# TBX01.net
KiCad netlist of a schematic drawn in EAGLE
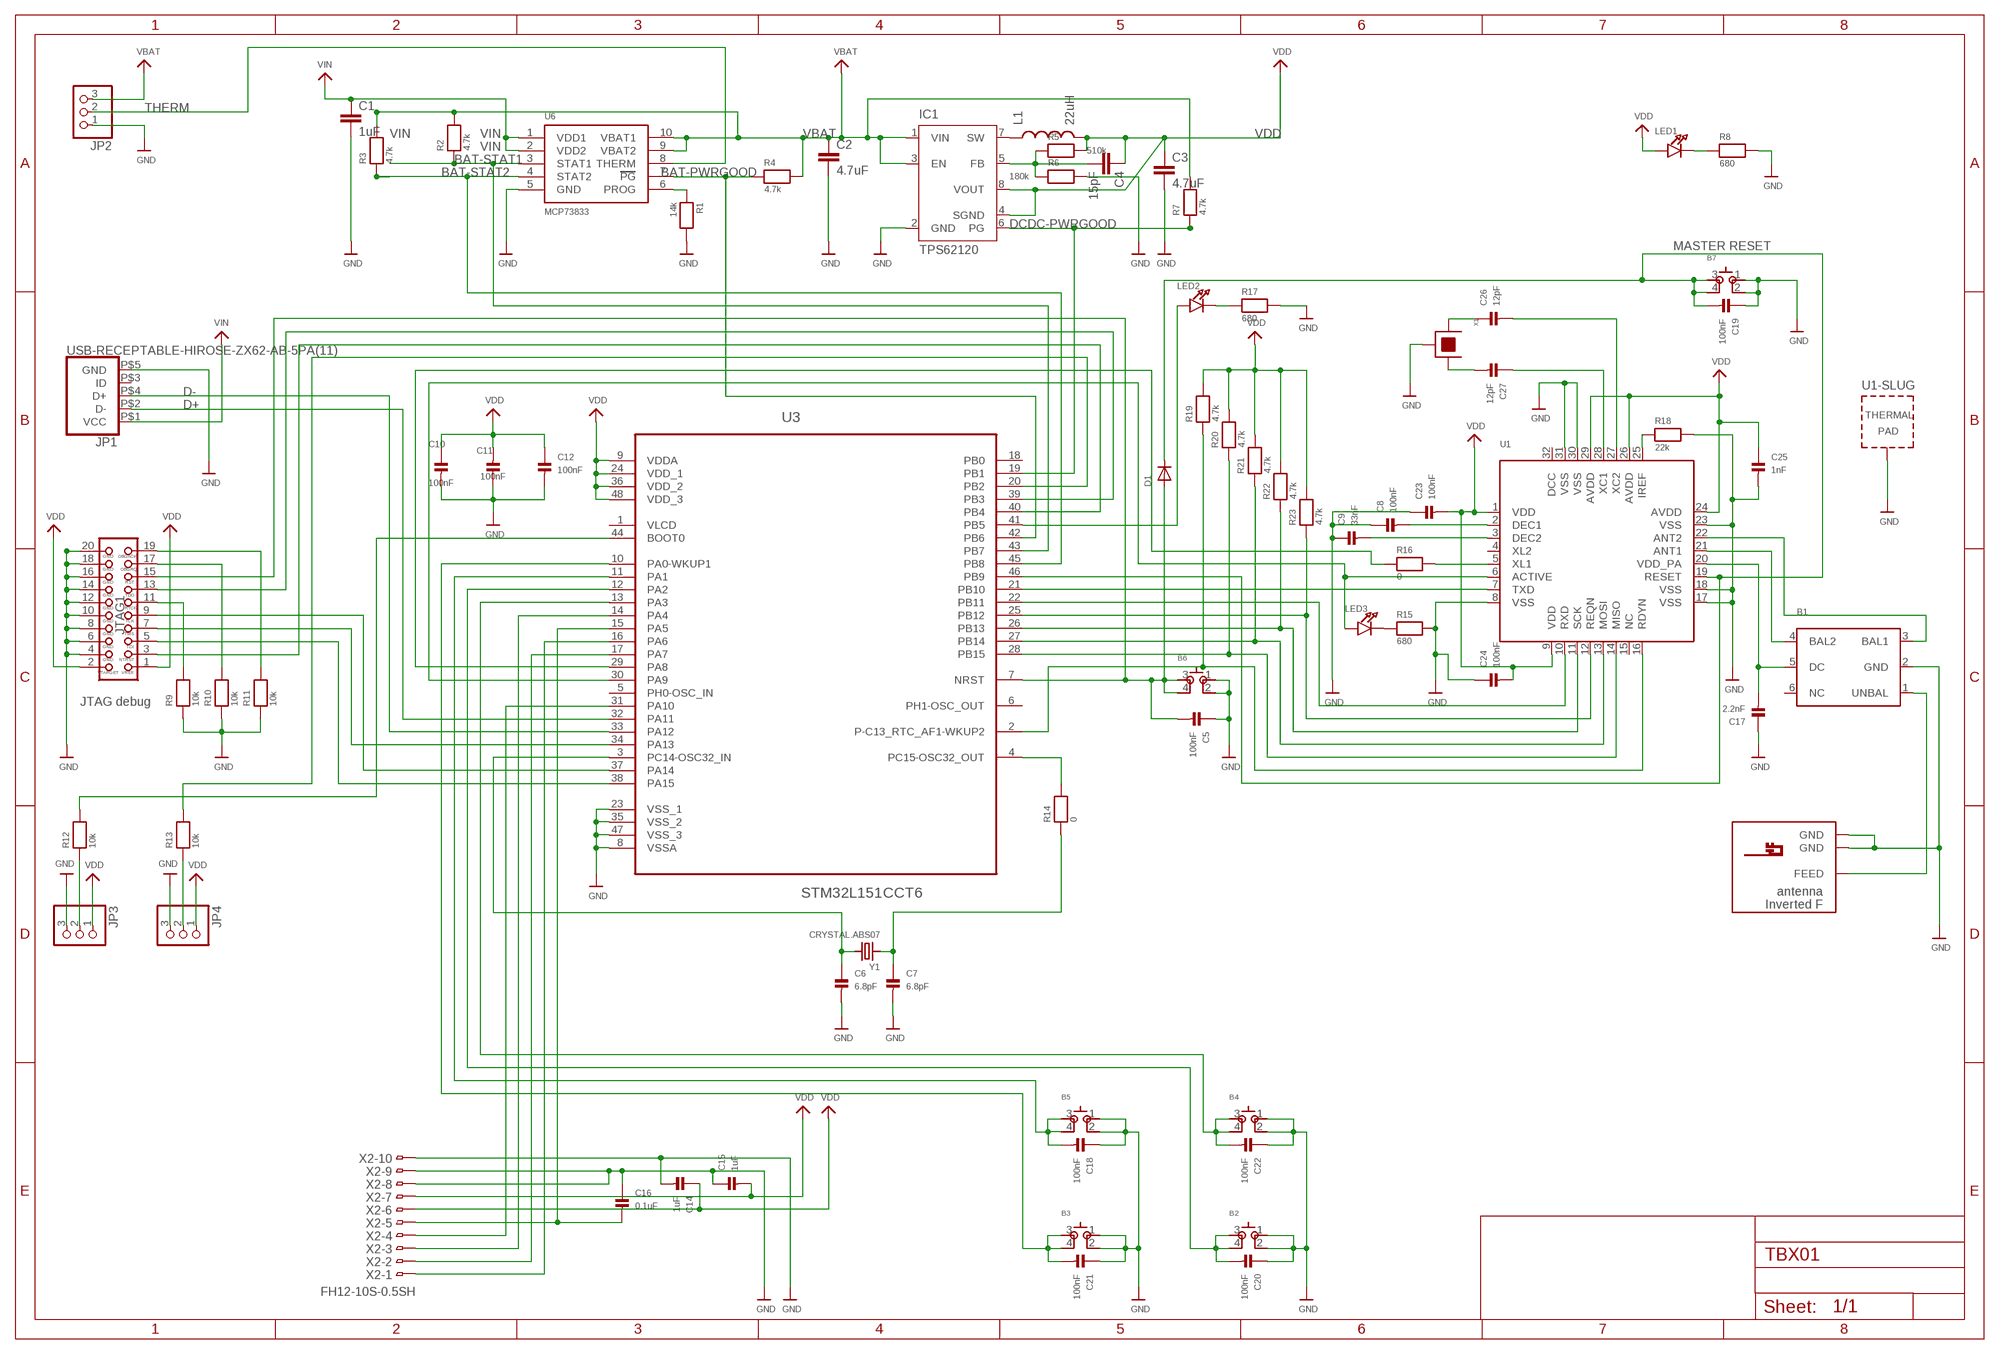
[diagram p0: schematic, sheet 1]

(export (version "E")
  (design (tool "Eeschema 10.0.6"))
  (components
    (comp (ref "B1")
      (value "BALUN+LP_NORDIC")
      (footprint "eagle-import:BALUN0603")
      (libsource (lib "eagle-import") (part "BALUN+LP_NORDIC"))
    )
    (comp (ref "B2")
      (value "SKSCLDE010")
      (footprint "eagle-import:SKSCLDE010")
      (libsource (lib "eagle-import") (part "SKSCLDE010"))
    )
    (comp (ref "B3")
      (value "SKSCLDE010")
      (footprint "eagle-import:SKSCLDE010")
      (libsource (lib "eagle-import") (part "SKSCLDE010"))
    )
    (comp (ref "B4")
      (value "SKSCLDE010")
      (footprint "eagle-import:SKSCLDE010")
      (libsource (lib "eagle-import") (part "SKSCLDE010"))
    )
    (comp (ref "B5")
      (value "SKSCLDE010")
      (footprint "eagle-import:SKSCLDE010")
      (libsource (lib "eagle-import") (part "SKSCLDE010"))
    )
    (comp (ref "B6")
      (value "SKSCLDE010")
      (footprint "eagle-import:SKSCLDE010")
      (libsource (lib "eagle-import") (part "SKSCLDE010"))
    )
    (comp (ref "B7")
      (value "SKSCLDE010")
      (footprint "eagle-import:SKSCLDE010")
      (libsource (lib "eagle-import") (part "SKSCLDE010"))
    )
    (comp (ref "C1")
      (value "1uF")
      (footprint "eagle-import:C0603")
      (libsource (lib "eagle-import") (part "C-EUC0603"))
    )
    (comp (ref "C2")
      (value "4.7uF")
      (footprint "eagle-import:C0603")
      (libsource (lib "eagle-import") (part "C-EUC0603"))
    )
    (comp (ref "C3")
      (value "4.7uF")
      (footprint "eagle-import:C0603")
      (libsource (lib "eagle-import") (part "C-EUC0603"))
    )
    (comp (ref "C4")
      (value "15pF")
      (footprint "eagle-import:C0603")
      (libsource (lib "eagle-import") (part "C-EUC0603"))
    )
    (comp (ref "C5")
      (value "100nF")
      (footprint "eagle-import:0603")
      (libsource (lib "eagle-import") (part "CAP_CERAMIC0603"))
    )
    (comp (ref "C6")
      (value "6.8pF")
      (footprint "eagle-import:0603")
      (libsource (lib "eagle-import") (part "CAP_CERAMIC0603"))
    )
    (comp (ref "C7")
      (value "6.8pF")
      (footprint "eagle-import:0603")
      (libsource (lib "eagle-import") (part "CAP_CERAMIC0603"))
    )
    (comp (ref "C8")
      (value "100nF")
      (footprint "eagle-import:0603")
      (libsource (lib "eagle-import") (part "CAP_CERAMIC0603"))
    )
    (comp (ref "C9")
      (value "33nF")
      (footprint "eagle-import:0603")
      (libsource (lib "eagle-import") (part "CAP_CERAMIC0603"))
    )
    (comp (ref "C10")
      (value "100nF")
      (footprint "eagle-import:0603")
      (libsource (lib "eagle-import") (part "CAP_CERAMIC0603"))
    )
    (comp (ref "C11")
      (value "100nF")
      (footprint "eagle-import:0603")
      (libsource (lib "eagle-import") (part "CAP_CERAMIC0603"))
    )
    (comp (ref "C12")
      (value "100nF")
      (footprint "eagle-import:0603")
      (libsource (lib "eagle-import") (part "CAP_CERAMIC0603"))
    )
    (comp (ref "C14")
      (value "1uF")
      (footprint "eagle-import:0603")
      (libsource (lib "eagle-import") (part "CAP_CERAMIC0603"))
    )
    (comp (ref "C15")
      (value "1uF")
      (footprint "eagle-import:0603")
      (libsource (lib "eagle-import") (part "CAP_CERAMIC0603"))
    )
    (comp (ref "C16")
      (value "0.1uF")
      (footprint "eagle-import:0603")
      (libsource (lib "eagle-import") (part "CAP_CERAMIC0603"))
    )
    (comp (ref "C17")
      (value "2.2nF")
      (footprint "eagle-import:0603")
      (libsource (lib "eagle-import") (part "CAP_CERAMIC0603"))
    )
    (comp (ref "C18")
      (value "100nF")
      (footprint "eagle-import:0603")
      (libsource (lib "eagle-import") (part "CAP_CERAMIC0603"))
    )
    (comp (ref "C19")
      (value "100nF")
      (footprint "eagle-import:0603")
      (libsource (lib "eagle-import") (part "CAP_CERAMIC0603"))
    )
    (comp (ref "C20")
      (value "100nF")
      (footprint "eagle-import:0603")
      (libsource (lib "eagle-import") (part "CAP_CERAMIC0603"))
    )
    (comp (ref "C21")
      (value "100nF")
      (footprint "eagle-import:0603")
      (libsource (lib "eagle-import") (part "CAP_CERAMIC0603"))
    )
    (comp (ref "C22")
      (value "100nF")
      (footprint "eagle-import:0603")
      (libsource (lib "eagle-import") (part "CAP_CERAMIC0603"))
    )
    (comp (ref "C23")
      (value "100nF")
      (footprint "eagle-import:0603")
      (libsource (lib "eagle-import") (part "CAP_CERAMIC0603"))
    )
    (comp (ref "C24")
      (value "100nF")
      (footprint "eagle-import:0603")
      (libsource (lib "eagle-import") (part "CAP_CERAMIC0603"))
    )
    (comp (ref "C25")
      (value "1nF")
      (footprint "eagle-import:0603")
      (libsource (lib "eagle-import") (part "CAP_CERAMIC0603"))
    )
    (comp (ref "C26")
      (value "12pF")
      (footprint "eagle-import:0603")
      (libsource (lib "eagle-import") (part "CAP_CERAMIC0603"))
    )
    (comp (ref "C27")
      (value "12pF")
      (footprint "eagle-import:0603")
      (libsource (lib "eagle-import") (part "CAP_CERAMIC0603"))
    )
    (comp (ref "D1")
      (value "DIODESOD-123")
      (footprint "eagle-import:SOD-123")
      (libsource (lib "eagle-import") (part "DIODESOD-123"))
    )
    (comp (ref "IC1")
      (value "TPS62120")
      (footprint "eagle-import:DCN-R-PDSO-G8")
      (libsource (lib "eagle-import") (part "TPS62120"))
    )
    (comp (ref "JP1")
      (value "USB-RECEPTABLE-HIROSE-ZX62-AB-5PA(11)")
      (footprint "eagle-import:HIROSE-ZX62-AB-5PA(11)")
      (libsource (lib "eagle-import") (part "USB-RECEPTABLE-HIROSE-ZX62-AB-5PA(11)"))
    )
    (comp (ref "JP2")
      (value "HEADER-1X3ROUND")
      (footprint "eagle-import:1X03_ROUND")
      (libsource (lib "eagle-import") (part "HEADER-1X3ROUND"))
    )
    (comp (ref "JP3")
      (value "HEADER-1X3ROUND")
      (footprint "eagle-import:1X03_ROUND")
      (libsource (lib "eagle-import") (part "HEADER-1X3ROUND"))
    )
    (comp (ref "JP4")
      (value "HEADER-1X3ROUND")
      (footprint "eagle-import:1X03_ROUND")
      (libsource (lib "eagle-import") (part "HEADER-1X3ROUND"))
    )
    (comp (ref "JTAG1")
      (value "JTAG-ARM")
      (footprint "eagle-import:JTAG-ARM")
      (libsource (lib "eagle-import") (part "JTAG-ARM"))
    )
    (comp (ref "L1")
      (value "22uH")
      (footprint "eagle-import:1210")
      (libsource (lib "eagle-import") (part "INDUCTOR1210"))
    )
    (comp (ref "LED1")
      (value "LED0603")
      (footprint "eagle-import:CHIPLED_0603")
      (libsource (lib "eagle-import") (part "LED0603"))
    )
    (comp (ref "LED2")
      (value "LED0603")
      (footprint "eagle-import:CHIPLED_0603")
      (libsource (lib "eagle-import") (part "LED0603"))
    )
    (comp (ref "LED3")
      (value "LED0603")
      (footprint "eagle-import:CHIPLED_0603")
      (libsource (lib "eagle-import") (part "LED0603"))
    )
    (comp (ref "R1")
      (value "14k")
      (footprint "eagle-import:0603")
      (libsource (lib "eagle-import") (part "RESISTOR0603"))
    )
    (comp (ref "R2")
      (value "4.7k")
      (footprint "eagle-import:0603")
      (libsource (lib "eagle-import") (part "RESISTOR0603"))
    )
    (comp (ref "R3")
      (value "4.7k")
      (footprint "eagle-import:0603")
      (libsource (lib "eagle-import") (part "RESISTOR0603"))
    )
    (comp (ref "R4")
      (value "4.7k")
      (footprint "eagle-import:0603")
      (libsource (lib "eagle-import") (part "RESISTOR0603"))
    )
    (comp (ref "R5")
      (value "510k")
      (footprint "eagle-import:0603")
      (libsource (lib "eagle-import") (part "RESISTOR0603"))
    )
    (comp (ref "R6")
      (value "180k")
      (footprint "eagle-import:0603")
      (libsource (lib "eagle-import") (part "RESISTOR0603"))
    )
    (comp (ref "R7")
      (value "4.7k")
      (footprint "eagle-import:0603")
      (libsource (lib "eagle-import") (part "RESISTOR0603"))
    )
    (comp (ref "R8")
      (value "680")
      (footprint "eagle-import:0603")
      (libsource (lib "eagle-import") (part "RESISTOR0603"))
    )
    (comp (ref "R9")
      (value "10k")
      (footprint "eagle-import:0603")
      (libsource (lib "eagle-import") (part "RESISTOR0603"))
    )
    (comp (ref "R10")
      (value "10k")
      (footprint "eagle-import:0603")
      (libsource (lib "eagle-import") (part "RESISTOR0603"))
    )
    (comp (ref "R11")
      (value "10k")
      (footprint "eagle-import:0603")
      (libsource (lib "eagle-import") (part "RESISTOR0603"))
    )
    (comp (ref "R12")
      (value "10k")
      (footprint "eagle-import:0603")
      (libsource (lib "eagle-import") (part "RESISTOR0603"))
    )
    (comp (ref "R13")
      (value "10k")
      (footprint "eagle-import:0603")
      (libsource (lib "eagle-import") (part "RESISTOR0603"))
    )
    (comp (ref "R14")
      (value "0")
      (footprint "eagle-import:0603")
      (libsource (lib "eagle-import") (part "RESISTOR0603"))
    )
    (comp (ref "R15")
      (value "680")
      (footprint "eagle-import:0603")
      (libsource (lib "eagle-import") (part "RESISTOR0603"))
    )
    (comp (ref "R16")
      (value "0")
      (footprint "eagle-import:0603")
      (libsource (lib "eagle-import") (part "RESISTOR0603"))
    )
    (comp (ref "R17")
      (value "680")
      (footprint "eagle-import:0603")
      (libsource (lib "eagle-import") (part "RESISTOR0603"))
    )
    (comp (ref "R18")
      (value "22k")
      (footprint "eagle-import:0603")
      (libsource (lib "eagle-import") (part "RESISTOR0603"))
    )
    (comp (ref "R19")
      (value "4.7k")
      (footprint "eagle-import:0603")
      (libsource (lib "eagle-import") (part "RESISTOR0603"))
    )
    (comp (ref "R20")
      (value "4.7k")
      (footprint "eagle-import:0603")
      (libsource (lib "eagle-import") (part "RESISTOR0603"))
    )
    (comp (ref "R21")
      (value "4.7k")
      (footprint "eagle-import:0603")
      (libsource (lib "eagle-import") (part "RESISTOR0603"))
    )
    (comp (ref "R22")
      (value "4.7k")
      (footprint "eagle-import:0603")
      (libsource (lib "eagle-import") (part "RESISTOR0603"))
    )
    (comp (ref "R23")
      (value "4.7k")
      (footprint "eagle-import:0603")
      (libsource (lib "eagle-import") (part "RESISTOR0603"))
    )
    (comp (ref "U$44")
      (value "INVERTED_F_ANTENNA+0")
      (footprint "eagle-import:DN007+0")
      (libsource (lib "eagle-import") (part "INVERTED_F_ANTENNA+0"))
    )
    (comp (ref "U1")
      (value "NRF8001")
      (footprint "eagle-import:QFN32_5MM")
      (libsource (lib "eagle-import") (part "NRF8001"))
    )
    (comp (ref "U3")
      (value "STM32L151CCT6")
      (footprint "eagle-import:QFP50P900X900X160-48N")
      (fields (field (name "MPN") "STM32L151CBT6"))
      (libsource (lib "eagle-import") (part "STM32L151CCT6"))
    )
    (comp (ref "U6")
      (value "MCP73833")
      (footprint "eagle-import:MSOP10")
      (libsource (lib "eagle-import") (part "MCP73833"))
    )
    (comp (ref "X1")
      (value "SHIELDED_CRYSTALTSX-3225")
      (footprint "eagle-import:TSX-3225")
      (libsource (lib "eagle-import") (part "SHIELDED_CRYSTALTSX-3225"))
    )
    (comp (ref "X2")
      (value "FH12-10S-0.5SH")
      (footprint "eagle-import:FH12-10S-0.5SH")
      (fields (field (name "MPN") "FH12-10S-0.5SH(55)"))
      (libsource (lib "eagle-import") (part "FH12-10S-0.5SH"))
    )
    (comp (ref "Y1")
      (value "CRYSTAL.ABS07")
      (footprint "eagle-import:ABS07")
      (libsource (lib "eagle-import") (part "CRYSTAL.ABS07"))
    )
  )
  (nets
    (net (code "1") (name "/BAT-PWRGOOD") (class "Default")
      (node (ref "R4") (pin "1") (pinfunction "1_1") (pintype "passive"))
      (node (ref "U3") (pin "42") (pinfunction "PB6_42") (pintype "bidirectional"))
      (node (ref "U6") (pin "7") (pinfunction "PG_7") (pintype "bidirectional"))
    )
    (net (code "2") (name "/BAT-STAT1") (class "Default")
      (node (ref "R2") (pin "1") (pinfunction "1_1") (pintype "passive"))
      (node (ref "U3") (pin "43") (pinfunction "PB7_43") (pintype "bidirectional"))
      (node (ref "U6") (pin "3") (pinfunction "STAT1_3") (pintype "bidirectional"))
    )
    (net (code "3") (name "/BAT-STAT2") (class "Default")
      (node (ref "R3") (pin "1") (pinfunction "1_1") (pintype "passive"))
      (node (ref "U3") (pin "45") (pinfunction "PB8_45") (pintype "bidirectional"))
      (node (ref "U6") (pin "4") (pinfunction "STAT2_4") (pintype "bidirectional"))
    )
    (net (code "4") (name "/D+") (class "Default")
      (node (ref "JP1") (pin "P$4") (pinfunction "D+_P$4") (pintype "bidirectional"))
      (node (ref "U3") (pin "33") (pinfunction "PA12_33") (pintype "bidirectional"))
    )
    (net (code "5") (name "/D-") (class "Default")
      (node (ref "JP1") (pin "P$2") (pinfunction "D-_P$2") (pintype "bidirectional"))
      (node (ref "U3") (pin "32") (pinfunction "PA11_32") (pintype "bidirectional"))
    )
    (net (code "6") (name "/DCDC-PWRGOOD") (class "Default")
      (node (ref "IC1") (pin "6") (pinfunction "PG_6") (pintype "passive"))
      (node (ref "R7") (pin "1") (pinfunction "1_1") (pintype "passive"))
      (node (ref "U3") (pin "19") (pinfunction "PB1_19") (pintype "bidirectional"))
    )
    (net (code "7") (name "/THERM") (class "Default")
      (node (ref "JP2") (pin "2") (pinfunction "2_2") (pintype "passive"))
      (node (ref "U6") (pin "8") (pinfunction "THERM_8") (pintype "bidirectional"))
    )
    (net (code "8") (name "/VLCD") (class "Default")
      (node (ref "U3") (pin "1") (pinfunction "VLCD_1") (pintype "power_in"))
    )
    (net (code "9") (name "GND") (class "Default")
      (node (ref "B1") (pin "2") (pinfunction "GND_2") (pintype "power_in"))
      (node (ref "B2") (pin "1") (pinfunction "4_1") (pintype "bidirectional"))
      (node (ref "B2") (pin "2") (pinfunction "3_2") (pintype "bidirectional"))
      (node (ref "B3") (pin "1") (pinfunction "4_1") (pintype "bidirectional"))
      (node (ref "B3") (pin "2") (pinfunction "3_2") (pintype "bidirectional"))
      (node (ref "B4") (pin "1") (pinfunction "4_1") (pintype "bidirectional"))
      (node (ref "B4") (pin "2") (pinfunction "3_2") (pintype "bidirectional"))
      (node (ref "B5") (pin "1") (pinfunction "4_1") (pintype "bidirectional"))
      (node (ref "B5") (pin "2") (pinfunction "3_2") (pintype "bidirectional"))
      (node (ref "B6") (pin "1") (pinfunction "4_1") (pintype "bidirectional"))
      (node (ref "B6") (pin "2") (pinfunction "3_2") (pintype "bidirectional"))
      (node (ref "B7") (pin "1") (pinfunction "4_1") (pintype "bidirectional"))
      (node (ref "B7") (pin "2") (pinfunction "3_2") (pintype "bidirectional"))
      (node (ref "C1") (pin "2") (pinfunction "2_2") (pintype "passive"))
      (node (ref "C10") (pin "2") (pinfunction "P$2_2") (pintype "passive"))
      (node (ref "C11") (pin "1") (pinfunction "P$1_1") (pintype "passive"))
      (node (ref "C12") (pin "2") (pinfunction "P$2_2") (pintype "passive"))
      (node (ref "C14") (pin "2") (pinfunction "P$2_2") (pintype "passive"))
      (node (ref "C15") (pin "1") (pinfunction "P$1_1") (pintype "passive"))
      (node (ref "C16") (pin "1") (pinfunction "P$1_1") (pintype "passive"))
      (node (ref "C17") (pin "1") (pinfunction "P$1_1") (pintype "passive"))
      (node (ref "C18") (pin "1") (pinfunction "P$1_1") (pintype "passive"))
      (node (ref "C19") (pin "1") (pinfunction "P$1_1") (pintype "passive"))
      (node (ref "C2") (pin "2") (pinfunction "2_2") (pintype "passive"))
      (node (ref "C20") (pin "1") (pinfunction "P$1_1") (pintype "passive"))
      (node (ref "C21") (pin "1") (pinfunction "P$1_1") (pintype "passive"))
      (node (ref "C22") (pin "1") (pinfunction "P$1_1") (pintype "passive"))
      (node (ref "C23") (pin "1") (pinfunction "P$1_1") (pintype "passive"))
      (node (ref "C24") (pin "1") (pinfunction "P$1_1") (pintype "passive"))
      (node (ref "C25") (pin "2") (pinfunction "P$2_2") (pintype "passive"))
      (node (ref "C3") (pin "2") (pinfunction "2_2") (pintype "passive"))
      (node (ref "C5") (pin "1") (pinfunction "P$1_1") (pintype "passive"))
      (node (ref "C6") (pin "2") (pinfunction "P$2_2") (pintype "passive"))
      (node (ref "C7") (pin "2") (pinfunction "P$2_2") (pintype "passive"))
      (node (ref "C8") (pin "1") (pinfunction "P$1_1") (pintype "passive"))
      (node (ref "C9") (pin "1") (pinfunction "P$1_1") (pintype "passive"))
      (node (ref "IC1") (pin "2") (pinfunction "GND_2") (pintype "power_in"))
      (node (ref "JP1") (pin "P$5") (pinfunction "GND_P$5") (pintype "bidirectional"))
      (node (ref "JP2") (pin "1") (pinfunction "1_1") (pintype "passive"))
      (node (ref "JP3") (pin "3") (pinfunction "3_3") (pintype "passive"))
      (node (ref "JP4") (pin "3") (pinfunction "3_3") (pintype "passive"))
      (node (ref "JTAG1") (pin "10") (pinfunction "10_10") (pintype "passive"))
      (node (ref "JTAG1") (pin "12") (pinfunction "12_12") (pintype "passive"))
      (node (ref "JTAG1") (pin "14") (pinfunction "14_14") (pintype "passive"))
      (node (ref "JTAG1") (pin "16") (pinfunction "16_16") (pintype "passive"))
      (node (ref "JTAG1") (pin "18") (pinfunction "18_18") (pintype "passive"))
      (node (ref "JTAG1") (pin "20") (pinfunction "20_20") (pintype "passive"))
      (node (ref "JTAG1") (pin "4") (pinfunction "4_4") (pintype "passive"))
      (node (ref "JTAG1") (pin "6") (pinfunction "6_6") (pintype "passive"))
      (node (ref "JTAG1") (pin "8") (pinfunction "8_8") (pintype "passive"))
      (node (ref "R1") (pin "2") (pinfunction "2_2") (pintype "passive"))
      (node (ref "R10") (pin "1") (pinfunction "1_1") (pintype "passive"))
      (node (ref "R11") (pin "1") (pinfunction "1_1") (pintype "passive"))
      (node (ref "R15") (pin "2") (pinfunction "2_2") (pintype "passive"))
      (node (ref "R17") (pin "2") (pinfunction "2_2") (pintype "passive"))
      (node (ref "R18") (pin "2") (pinfunction "2_2") (pintype "passive"))
      (node (ref "R6") (pin "2") (pinfunction "2_2") (pintype "passive"))
      (node (ref "R8") (pin "2") (pinfunction "2_2") (pintype "passive"))
      (node (ref "R9") (pin "1") (pinfunction "1_1") (pintype "passive"))
      (node (ref "U$44") (pin "GND") (pinfunction "GND_GND") (pintype "bidirectional"))
      (node (ref "U$44") (pin "GND@1") (pinfunction "GND_GND@1") (pintype "bidirectional"))
      (node (ref "U1") (pin "17") (pinfunction "VSS_17") (pintype "power_in"))
      (node (ref "U1") (pin "18") (pinfunction "VSS_18") (pintype "power_in"))
      (node (ref "U1") (pin "23") (pinfunction "VSS_23") (pintype "power_in"))
      (node (ref "U1") (pin "30") (pinfunction "VSS_30") (pintype "power_in"))
      (node (ref "U1") (pin "31") (pinfunction "VSS_31") (pintype "power_in"))
      (node (ref "U1") (pin "8") (pinfunction "VSS_8") (pintype "power_in"))
      (node (ref "U1") (pin "GND") (pinfunction "TP_GND") (pintype "power_in"))
      (node (ref "U3") (pin "23") (pinfunction "VSS_1_23") (pintype "power_in"))
      (node (ref "U3") (pin "35") (pinfunction "VSS_2_35") (pintype "power_in"))
      (node (ref "U3") (pin "47") (pinfunction "VSS_3_47") (pintype "power_in"))
      (node (ref "U3") (pin "8") (pinfunction "VSSA_8") (pintype "power_in"))
      (node (ref "U6") (pin "5") (pinfunction "GND_5") (pintype "bidirectional"))
      (node (ref "X1") (pin "2") (pinfunction "P$3_2") (pintype "bidirectional"))
      (node (ref "X1") (pin "4") (pinfunction "P$3_4") (pintype "bidirectional"))
      (node (ref "X2") (pin "10") (pinfunction "1_10") (pintype "passive"))
      (node (ref "X2") (pin "8") (pinfunction "1_8") (pintype "passive"))
      (node (ref "X2") (pin "9") (pinfunction "1_9") (pintype "passive"))
    )
    (net (code "10") (name "Net-(B1-BAL1)") (class "Default")
      (node (ref "B1") (pin "3") (pinfunction "BAL1_3") (pintype "bidirectional"))
      (node (ref "U1") (pin "22") (pinfunction "ANT2_22") (pintype "bidirectional"))
    )
    (net (code "11") (name "Net-(B1-BAL2)") (class "Default")
      (node (ref "B1") (pin "4") (pinfunction "BAL2_4") (pintype "bidirectional"))
      (node (ref "U1") (pin "21") (pinfunction "ANT1_21") (pintype "bidirectional"))
    )
    (net (code "12") (name "Net-(B1-DC)") (class "Default")
      (node (ref "B1") (pin "5") (pinfunction "DC_5") (pintype "bidirectional"))
      (node (ref "C17") (pin "2") (pinfunction "P$2_2") (pintype "passive"))
      (node (ref "U1") (pin "20") (pinfunction "VDD_PA_20") (pintype "bidirectional"))
    )
    (net (code "13") (name "Net-(B1-UNBAL)") (class "Default")
      (node (ref "B1") (pin "1") (pinfunction "UNBAL_1") (pintype "bidirectional"))
      (node (ref "U$44") (pin "FEED") (pinfunction "FEED_FEED") (pintype "bidirectional"))
    )
    (net (code "14") (name "Net-(B2-1)") (class "Default")
      (node (ref "B2") (pin "3") (pinfunction "1_3") (pintype "bidirectional"))
      (node (ref "B2") (pin "4") (pinfunction "2_4") (pintype "bidirectional"))
      (node (ref "C20") (pin "2") (pinfunction "P$2_2") (pintype "passive"))
      (node (ref "U3") (pin "12") (pinfunction "PA2_12") (pintype "bidirectional"))
    )
    (net (code "15") (name "Net-(B3-1)") (class "Default")
      (node (ref "B3") (pin "3") (pinfunction "1_3") (pintype "bidirectional"))
      (node (ref "B3") (pin "4") (pinfunction "2_4") (pintype "bidirectional"))
      (node (ref "C21") (pin "2") (pinfunction "P$2_2") (pintype "passive"))
      (node (ref "U3") (pin "10") (pinfunction "PA0-WKUP1_10") (pintype "bidirectional"))
    )
    (net (code "16") (name "Net-(B4-1)") (class "Default")
      (node (ref "B4") (pin "3") (pinfunction "1_3") (pintype "bidirectional"))
      (node (ref "B4") (pin "4") (pinfunction "2_4") (pintype "bidirectional"))
      (node (ref "C22") (pin "2") (pinfunction "P$2_2") (pintype "passive"))
      (node (ref "U3") (pin "13") (pinfunction "PA3_13") (pintype "bidirectional"))
    )
    (net (code "17") (name "Net-(B5-1)") (class "Default")
      (node (ref "B5") (pin "3") (pinfunction "1_3") (pintype "bidirectional"))
      (node (ref "B5") (pin "4") (pinfunction "2_4") (pintype "bidirectional"))
      (node (ref "C18") (pin "2") (pinfunction "P$2_2") (pintype "passive"))
      (node (ref "U3") (pin "11") (pinfunction "PA1_11") (pintype "bidirectional"))
    )
    (net (code "18") (name "Net-(B6-1)") (class "Default")
      (node (ref "B6") (pin "3") (pinfunction "1_3") (pintype "bidirectional"))
      (node (ref "B6") (pin "4") (pinfunction "2_4") (pintype "bidirectional"))
      (node (ref "C5") (pin "2") (pinfunction "P$2_2") (pintype "passive"))
      (node (ref "D1") (pin "A") (pinfunction "A_A") (pintype "passive"))
      (node (ref "JTAG1") (pin "15") (pinfunction "15_15") (pintype "passive"))
      (node (ref "U3") (pin "7") (pinfunction "NRST_7") (pintype "bidirectional"))
    )
    (net (code "19") (name "Net-(B7-1)") (class "Default")
      (node (ref "B7") (pin "3") (pinfunction "1_3") (pintype "bidirectional"))
      (node (ref "B7") (pin "4") (pinfunction "2_4") (pintype "bidirectional"))
      (node (ref "C19") (pin "2") (pinfunction "P$2_2") (pintype "passive"))
      (node (ref "D1") (pin "C") (pinfunction "C_C") (pintype "passive"))
      (node (ref "U1") (pin "19") (pinfunction "RESET_19") (pintype "input"))
      (node (ref "U3") (pin "46") (pinfunction "PB9_46") (pintype "bidirectional"))
    )
    (net (code "20") (name "Net-(C6-P$1)") (class "Default")
      (node (ref "C6") (pin "1") (pinfunction "P$1_1") (pintype "passive"))
      (node (ref "U3") (pin "3") (pinfunction "PC14-OSC32_IN_3") (pintype "input"))
      (node (ref "Y1") (pin "2") (pinfunction "2_2") (pintype "passive"))
    )
    (net (code "21") (name "Net-(C7-P$1)") (class "Default")
      (node (ref "C7") (pin "1") (pinfunction "P$1_1") (pintype "passive"))
      (node (ref "R14") (pin "1") (pinfunction "1_1") (pintype "passive"))
      (node (ref "Y1") (pin "1") (pinfunction "1_1") (pintype "passive"))
    )
    (net (code "22") (name "Net-(C8-P$2)") (class "Default")
      (node (ref "C8") (pin "2") (pinfunction "P$2_2") (pintype "passive"))
      (node (ref "U1") (pin "2") (pinfunction "DEC1_2") (pintype "bidirectional"))
    )
    (net (code "23") (name "Net-(C9-P$2)") (class "Default")
      (node (ref "C9") (pin "2") (pinfunction "P$2_2") (pintype "passive"))
      (node (ref "U1") (pin "3") (pinfunction "DEC2_3") (pintype "bidirectional"))
    )
    (net (code "24") (name "Net-(C16-P$2)") (class "Default")
      (node (ref "C16") (pin "2") (pinfunction "P$2_2") (pintype "passive"))
      (node (ref "U3") (pin "15") (pinfunction "PA5_15") (pintype "bidirectional"))
      (node (ref "X2") (pin "5") (pinfunction "1_5") (pintype "passive"))
    )
    (net (code "25") (name "Net-(C26-P$1)") (class "Default")
      (node (ref "C26") (pin "1") (pinfunction "P$1_1") (pintype "passive"))
      (node (ref "X1") (pin "1") (pinfunction "P$1_1") (pintype "bidirectional"))
    )
    (net (code "26") (name "Net-(C26-P$2)") (class "Default")
      (node (ref "C26") (pin "2") (pinfunction "P$2_2") (pintype "passive"))
      (node (ref "U1") (pin "27") (pinfunction "XC2_27") (pintype "output"))
    )
    (net (code "27") (name "Net-(C27-P$1)") (class "Default")
      (node (ref "C27") (pin "1") (pinfunction "P$1_1") (pintype "passive"))
      (node (ref "U1") (pin "28") (pinfunction "XC1_28") (pintype "input"))
    )
    (net (code "28") (name "Net-(C27-P$2)") (class "Default")
      (node (ref "C27") (pin "2") (pinfunction "P$2_2") (pintype "passive"))
      (node (ref "X1") (pin "3") (pinfunction "P$2_3") (pintype "bidirectional"))
    )
    (net (code "29") (name "Net-(IC1-FB)") (class "Default")
      (node (ref "C4") (pin "2") (pinfunction "2_2") (pintype "passive"))
      (node (ref "IC1") (pin "5") (pinfunction "FB_5") (pintype "input"))
      (node (ref "R5") (pin "1") (pinfunction "1_1") (pintype "passive"))
      (node (ref "R6") (pin "1") (pinfunction "1_1") (pintype "passive"))
    )
    (net (code "30") (name "Net-(IC1-SW)") (class "Default")
      (node (ref "IC1") (pin "7") (pinfunction "SW_7") (pintype "output"))
      (node (ref "L1") (pin "1") (pinfunction "1_1") (pintype "passive"))
    )
    (net (code "31") (name "Net-(JP3-Pad2)") (class "Default")
      (node (ref "JP3") (pin "2") (pinfunction "2_2") (pintype "passive"))
      (node (ref "R12") (pin "1") (pinfunction "1_1") (pintype "passive"))
    )
    (net (code "32") (name "Net-(JP4-Pad2)") (class "Default")
      (node (ref "JP4") (pin "2") (pinfunction "2_2") (pintype "passive"))
      (node (ref "R13") (pin "1") (pinfunction "1_1") (pintype "passive"))
    )
    (net (code "33") (name "Net-(JTAG1-Pad11)") (class "Default")
      (node (ref "JTAG1") (pin "11") (pinfunction "11_11") (pintype "passive"))
      (node (ref "R9") (pin "2") (pinfunction "2_2") (pintype "passive"))
    )
    (net (code "34") (name "Net-(JTAG1-Pad17)") (class "Default")
      (node (ref "JTAG1") (pin "17") (pinfunction "17_17") (pintype "passive"))
      (node (ref "R10") (pin "2") (pinfunction "2_2") (pintype "passive"))
    )
    (net (code "35") (name "Net-(JTAG1-Pad19)") (class "Default")
      (node (ref "JTAG1") (pin "19") (pinfunction "19_19") (pintype "passive"))
      (node (ref "R11") (pin "2") (pinfunction "2_2") (pintype "passive"))
    )
    (net (code "36") (name "Net-(LED1-PadC)") (class "Default")
      (node (ref "LED1") (pin "C") (pinfunction "C_C") (pintype "passive"))
      (node (ref "R8") (pin "1") (pinfunction "1_1") (pintype "passive"))
    )
    (net (code "37") (name "Net-(LED2-PadC)") (class "Default")
      (node (ref "LED2") (pin "C") (pinfunction "C_C") (pintype "passive"))
      (node (ref "R17") (pin "1") (pinfunction "1_1") (pintype "passive"))
    )
    (net (code "38") (name "Net-(LED3-PadC)") (class "Default")
      (node (ref "LED3") (pin "C") (pinfunction "C_C") (pintype "passive"))
      (node (ref "R15") (pin "1") (pinfunction "1_1") (pintype "passive"))
    )
    (net (code "39") (name "Net-(U1B-ACTIVE)") (class "Default")
      (node (ref "LED3") (pin "A") (pinfunction "A_A") (pintype "passive"))
      (node (ref "U1") (pin "6") (pinfunction "ACTIVE_6") (pintype "output"))
      (node (ref "U3") (pin "30") (pinfunction "PA9_30") (pintype "bidirectional"))
    )
    (net (code "40") (name "Net-(U1B-IREF)") (class "Default")
      (node (ref "R18") (pin "1") (pinfunction "1_1") (pintype "passive"))
      (node (ref "U1") (pin "25") (pinfunction "IREF_25") (pintype "output"))
    )
    (net (code "41") (name "Net-(U1B-MISO)") (class "Default")
      (node (ref "R20") (pin "1") (pinfunction "1_1") (pintype "passive"))
      (node (ref "U1") (pin "14") (pinfunction "MISO_14") (pintype "output"))
      (node (ref "U3") (pin "28") (pinfunction "PB15_28") (pintype "bidirectional"))
    )
    (net (code "42") (name "Net-(U1B-MOSI)") (class "Default")
      (node (ref "R21") (pin "1") (pinfunction "1_1") (pintype "passive"))
      (node (ref "U1") (pin "13") (pinfunction "MOSI_13") (pintype "input"))
      (node (ref "U3") (pin "27") (pinfunction "PB14_27") (pintype "bidirectional"))
    )
    (net (code "43") (name "Net-(U1B-RDYN)") (class "Default")
      (node (ref "R19") (pin "1") (pinfunction "1_1") (pintype "passive"))
      (node (ref "U1") (pin "16") (pinfunction "RDYN_16") (pintype "output"))
      (node (ref "U3") (pin "2") (pinfunction "P-C13_RTC_AF1-WKUP2_2") (pintype "bidirectional"))
    )
    (net (code "44") (name "Net-(U1B-REQN)") (class "Default")
      (node (ref "R23") (pin "1") (pinfunction "1_1") (pintype "passive"))
      (node (ref "U1") (pin "12") (pinfunction "REQN_12") (pintype "input"))
      (node (ref "U3") (pin "25") (pinfunction "PB12_25") (pintype "bidirectional"))
    )
    (net (code "45") (name "Net-(U1B-RXD)") (class "Default")
      (node (ref "U1") (pin "10") (pinfunction "RXD_10") (pintype "input"))
      (node (ref "U3") (pin "22") (pinfunction "PB11_22") (pintype "bidirectional"))
    )
    (net (code "46") (name "Net-(U1B-SCK)") (class "Default")
      (node (ref "R22") (pin "1") (pinfunction "1_1") (pintype "passive"))
      (node (ref "U1") (pin "11") (pinfunction "SCK_11") (pintype "input"))
      (node (ref "U3") (pin "26") (pinfunction "PB13_26") (pintype "bidirectional"))
    )
    (net (code "47") (name "Net-(U1B-TXD)") (class "Default")
      (node (ref "U1") (pin "7") (pinfunction "TXD_7") (pintype "output"))
      (node (ref "U3") (pin "21") (pinfunction "PB10_21") (pintype "bidirectional"))
    )
    (net (code "48") (name "Net-(U1B-XL1)") (class "Default")
      (node (ref "R16") (pin "2") (pinfunction "2_2") (pintype "passive"))
      (node (ref "U1") (pin "5") (pinfunction "XL1_5") (pintype "input"))
    )
    (net (code "49") (name "Net-(U3-BOOT0)") (class "Default")
      (node (ref "R12") (pin "2") (pinfunction "2_2") (pintype "passive"))
      (node (ref "U3") (pin "44") (pinfunction "BOOT0_44") (pintype "input"))
    )
    (net (code "50") (name "Net-(U3-PA4)") (class "Default")
      (node (ref "U3") (pin "14") (pinfunction "PA4_14") (pintype "bidirectional"))
      (node (ref "X2") (pin "3") (pinfunction "1_3") (pintype "passive"))
    )
    (net (code "51") (name "Net-(U3-PA6)") (class "Default")
      (node (ref "U3") (pin "16") (pinfunction "PA6_16") (pintype "bidirectional"))
      (node (ref "X2") (pin "1") (pinfunction "1_1") (pintype "passive"))
    )
    (net (code "52") (name "Net-(U3-PA7)") (class "Default")
      (node (ref "U3") (pin "17") (pinfunction "PA7_17") (pintype "bidirectional"))
      (node (ref "X2") (pin "2") (pinfunction "1_2") (pintype "passive"))
    )
    (net (code "53") (name "Net-(U3-PA8)") (class "Default")
      (node (ref "R16") (pin "1") (pinfunction "1_1") (pintype "passive"))
      (node (ref "U3") (pin "29") (pinfunction "PA8_29") (pintype "bidirectional"))
    )
    (net (code "54") (name "Net-(U3-PA10)") (class "Default")
      (node (ref "U3") (pin "31") (pinfunction "PA10_31") (pintype "bidirectional"))
      (node (ref "X2") (pin "4") (pinfunction "1_4") (pintype "passive"))
    )
    (net (code "55") (name "Net-(U3-PA13)") (class "Default")
      (node (ref "JTAG1") (pin "7") (pinfunction "7_7") (pintype "passive"))
      (node (ref "U3") (pin "34") (pinfunction "PA13_34") (pintype "bidirectional"))
    )
    (net (code "56") (name "Net-(U3-PA14)") (class "Default")
      (node (ref "JTAG1") (pin "9") (pinfunction "9_9") (pintype "passive"))
      (node (ref "U3") (pin "37") (pinfunction "PA14_37") (pintype "bidirectional"))
    )
    (net (code "57") (name "Net-(U3-PA15)") (class "Default")
      (node (ref "JTAG1") (pin "5") (pinfunction "5_5") (pintype "passive"))
      (node (ref "U3") (pin "38") (pinfunction "PA15_38") (pintype "bidirectional"))
    )
    (net (code "58") (name "Net-(U3-PB2)") (class "Default")
      (node (ref "R13") (pin "2") (pinfunction "2_2") (pintype "passive"))
      (node (ref "U3") (pin "20") (pinfunction "PB2_20") (pintype "bidirectional"))
    )
    (net (code "59") (name "Net-(U3-PB3)") (class "Default")
      (node (ref "JTAG1") (pin "13") (pinfunction "13_13") (pintype "passive"))
      (node (ref "U3") (pin "39") (pinfunction "PB3_39") (pintype "bidirectional"))
    )
    (net (code "60") (name "Net-(U3-PB4)") (class "Default")
      (node (ref "JTAG1") (pin "3") (pinfunction "3_3") (pintype "passive"))
      (node (ref "U3") (pin "40") (pinfunction "PB4_40") (pintype "bidirectional"))
    )
    (net (code "61") (name "Net-(U3-PB5)") (class "Default")
      (node (ref "LED2") (pin "A") (pinfunction "A_A") (pintype "passive"))
      (node (ref "U3") (pin "41") (pinfunction "PB5_41") (pintype "bidirectional"))
    )
    (net (code "62") (name "Net-(U3-PC15-OSC32_OUT)") (class "Default")
      (node (ref "R14") (pin "2") (pinfunction "2_2") (pintype "passive"))
      (node (ref "U3") (pin "4") (pinfunction "PC15-OSC32_OUT_4") (pintype "output"))
    )
    (net (code "63") (name "Net-(U6-PROG)") (class "Default")
      (node (ref "R1") (pin "1") (pinfunction "1_1") (pintype "passive"))
      (node (ref "U6") (pin "6") (pinfunction "PROG_6") (pintype "bidirectional"))
    )
    (net (code "64") (name "VBAT") (class "Default")
      (node (ref "C2") (pin "1") (pinfunction "1_1") (pintype "passive"))
      (node (ref "IC1") (pin "1") (pinfunction "VIN_1") (pintype "input"))
      (node (ref "IC1") (pin "3") (pinfunction "EN_3") (pintype "input"))
      (node (ref "JP2") (pin "3") (pinfunction "3_3") (pintype "passive"))
      (node (ref "R2") (pin "2") (pinfunction "2_2") (pintype "passive"))
      (node (ref "R3") (pin "2") (pinfunction "2_2") (pintype "passive"))
      (node (ref "R4") (pin "2") (pinfunction "2_2") (pintype "passive"))
      (node (ref "R7") (pin "2") (pinfunction "2_2") (pintype "passive"))
      (node (ref "U6") (pin "10") (pinfunction "VBAT1_10") (pintype "bidirectional"))
      (node (ref "U6") (pin "9") (pinfunction "VBAT2_9") (pintype "bidirectional"))
    )
    (net (code "65") (name "VDD") (class "Default")
      (node (ref "C10") (pin "1") (pinfunction "P$1_1") (pintype "passive"))
      (node (ref "C11") (pin "2") (pinfunction "P$2_2") (pintype "passive"))
      (node (ref "C12") (pin "1") (pinfunction "P$1_1") (pintype "passive"))
      (node (ref "C14") (pin "1") (pinfunction "P$1_1") (pintype "passive"))
      (node (ref "C15") (pin "2") (pinfunction "P$2_2") (pintype "passive"))
      (node (ref "C23") (pin "2") (pinfunction "P$2_2") (pintype "passive"))
      (node (ref "C24") (pin "2") (pinfunction "P$2_2") (pintype "passive"))
      (node (ref "C25") (pin "1") (pinfunction "P$1_1") (pintype "passive"))
      (node (ref "C3") (pin "1") (pinfunction "1_1") (pintype "passive"))
      (node (ref "C4") (pin "1") (pinfunction "1_1") (pintype "passive"))
      (node (ref "IC1") (pin "4") (pinfunction "SGND_4") (pintype "passive"))
      (node (ref "IC1") (pin "8") (pinfunction "VOUT_8") (pintype "output"))
      (node (ref "JP3") (pin "1") (pinfunction "1_1") (pintype "passive"))
      (node (ref "JP4") (pin "1") (pinfunction "1_1") (pintype "passive"))
      (node (ref "JTAG1") (pin "1") (pinfunction "1_1") (pintype "passive"))
      (node (ref "JTAG1") (pin "2") (pinfunction "2_2") (pintype "passive"))
      (node (ref "L1") (pin "2") (pinfunction "2_2") (pintype "passive"))
      (node (ref "LED1") (pin "A") (pinfunction "A_A") (pintype "passive"))
      (node (ref "R19") (pin "2") (pinfunction "2_2") (pintype "passive"))
      (node (ref "R20") (pin "2") (pinfunction "2_2") (pintype "passive"))
      (node (ref "R21") (pin "2") (pinfunction "2_2") (pintype "passive"))
      (node (ref "R22") (pin "2") (pinfunction "2_2") (pintype "passive"))
      (node (ref "R23") (pin "2") (pinfunction "2_2") (pintype "passive"))
      (node (ref "R5") (pin "2") (pinfunction "2_2") (pintype "passive"))
      (node (ref "U1") (pin "1") (pinfunction "VDD_1") (pintype "power_in"))
      (node (ref "U1") (pin "24") (pinfunction "AVDD_24") (pintype "power_in"))
      (node (ref "U1") (pin "26") (pinfunction "AVDD_26") (pintype "power_in"))
      (node (ref "U1") (pin "29") (pinfunction "AVDD_29") (pintype "power_in"))
      (node (ref "U1") (pin "9") (pinfunction "VDD_9") (pintype "power_in"))
      (node (ref "U3") (pin "24") (pinfunction "VDD_1_24") (pintype "power_in"))
      (node (ref "U3") (pin "36") (pinfunction "VDD_2_36") (pintype "power_in"))
      (node (ref "U3") (pin "48") (pinfunction "VDD_3_48") (pintype "power_in"))
      (node (ref "U3") (pin "9") (pinfunction "VDDA_9") (pintype "power_in"))
      (node (ref "X2") (pin "6") (pinfunction "1_6") (pintype "passive"))
      (node (ref "X2") (pin "7") (pinfunction "1_7") (pintype "passive"))
    )
    (net (code "66") (name "VIN") (class "Default")
      (node (ref "C1") (pin "1") (pinfunction "1_1") (pintype "passive"))
      (node (ref "JP1") (pin "P$1") (pinfunction "VCC_P$1") (pintype "bidirectional"))
      (node (ref "U6") (pin "1") (pinfunction "VDD1_1") (pintype "bidirectional"))
      (node (ref "U6") (pin "2") (pinfunction "VDD2_2") (pintype "bidirectional"))
    )
    (net (code "67") (name "unconnected-(B1-NC-Pad6)") (class "Default")
      (node (ref "B1") (pin "6") (pinfunction "NC_6") (pintype "no_connect"))
    )
    (net (code "68") (name "unconnected-(JP1-ID-PadP$3)") (class "Default")
      (node (ref "JP1") (pin "P$3") (pinfunction "ID_P$3") (pintype "bidirectional"))
    )
    (net (code "69") (name "unconnected-(U1B-DCC-Pad32)") (class "Default")
      (node (ref "U1") (pin "32") (pinfunction "DCC_32") (pintype "bidirectional"))
    )
    (net (code "70") (name "unconnected-(U1B-NC-Pad15)") (class "Default")
      (node (ref "U1") (pin "15") (pinfunction "NC_15") (pintype "no_connect"))
    )
    (net (code "71") (name "unconnected-(U1B-XL2-Pad4)") (class "Default")
      (node (ref "U1") (pin "4") (pinfunction "XL2_4") (pintype "output"))
    )
    (net (code "72") (name "unconnected-(U3-PB0-Pad18)") (class "Default")
      (node (ref "U3") (pin "18") (pinfunction "PB0_18") (pintype "bidirectional"))
    )
    (net (code "73") (name "unconnected-(U3-PH0-OSC_IN-Pad5)") (class "Default")
      (node (ref "U3") (pin "5") (pinfunction "PH0-OSC_IN_5") (pintype "input"))
    )
    (net (code "74") (name "unconnected-(U3-PH1-OSC_OUT-Pad6)") (class "Default")
      (node (ref "U3") (pin "6") (pinfunction "PH1-OSC_OUT_6") (pintype "output"))
    )
  )
)
